# HomeLedEncoder.net
KiCad netlist of a schematic drawn in Altium Designer
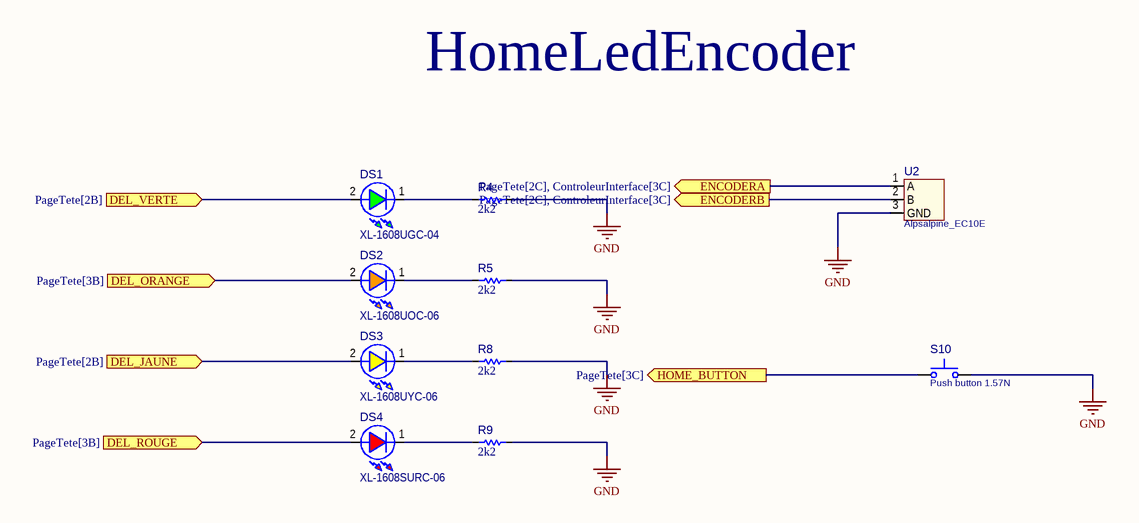
[diagram p0: HomeLedEncoder.SchDoc]

(export (version "E")
  (design (tool "Eeschema 10.0.6"))
  (components
    (comp (ref "DS1")
      (value "XL-1608UGC-04")
      (footprint "D_LED_0603")
      (description "LED Green Clear 40mcd 140deg")
      (libsource (lib "243-336_MP_Manette_ETU") (part "D_LED_GREEN_0603"))
    )
    (comp (ref "DS2")
      (value "XL-1608UOC-06")
      (footprint "D_LED_0603")
      (description "LED Orange Clear")
      (libsource (lib "243-336_MP_Manette_ETU") (part "D_LED_ORANGE_0603"))
    )
    (comp (ref "DS3")
      (value "XL-1608UYC-06")
      (footprint "D_LED_0603")
      (description "LED Yellow Clear")
      (libsource (lib "243-336_MP_Manette_ETU") (part "D_LED_YELLOW_0603"))
    )
    (comp (ref "DS4")
      (value "XL-1608SURC-06")
      (footprint "D_LED_0603")
      (description "LED Red Clear 60mcd 140deg")
      (libsource (lib "243-336_MP_Manette_ETU") (part "D_LED_RED_0603"))
    )
    (comp (ref "R4")
      (value "2k2")
      (footprint "R_1005[0402]")
      (description "Resistor type 1")
      (fields (field (name "TOLERANCE") "1%") (field (name "Comment") "Res 2k2 1% 0402"))
      (libsource (lib "TEP_243-Altium_RLC-Lib") (part "RES008"))
    )
    (comp (ref "R5")
      (value "2k2")
      (footprint "R_1005[0402]")
      (description "Resistor type 1")
      (fields (field (name "TOLERANCE") "1%") (field (name "Comment") "Res 2k2 1% 0402"))
      (libsource (lib "TEP_243-Altium_RLC-Lib") (part "RES008"))
    )
    (comp (ref "R8")
      (value "2k2")
      (footprint "R_1005[0402]")
      (description "Resistor type 1")
      (fields (field (name "TOLERANCE") "1%") (field (name "Comment") "Res 2k2 1% 0402"))
      (libsource (lib "TEP_243-Altium_RLC-Lib") (part "RES008"))
    )
    (comp (ref "R9")
      (value "2k2")
      (footprint "R_1005[0402]")
      (description "Resistor type 1")
      (fields (field (name "TOLERANCE") "1%") (field (name "Comment") "Res 2k2 1% 0402"))
      (libsource (lib "TEP_243-Altium_RLC-Lib") (part "RES008"))
    )
    (comp (ref "S10")
      (value "Push button 1.57N")
      (footprint "S_Alpsalpine_SKPM")
      (fields (field (name "Comment") "SKPMAME010"))
      (libsource (lib "243-336_MP_Manette_ETU") (part "SW_Push_SKPM_157N"))
    )
    (comp (ref "U2")
      (value "Alpsalpine_EC10E")
      (footprint "U_Alpsalpine_EC10E")
      (description "Rotary Encoder TH")
      (fields (field (name "Comment") "EC10E1220503"))
      (libsource (lib "243-336_MP_Manette_ETU") (part "U_Alpsalpine_EC10E"))
    )
  )
  (nets
    (net (code "1") (name "/DEL_JAUNE") (class "Default")
      (node (ref "DS3") (pin "2") (pinfunction "A_2") (pintype "passive"))
    )
    (net (code "2") (name "/DEL_ORANGE") (class "Default")
      (node (ref "DS2") (pin "2") (pinfunction "A_2") (pintype "passive"))
    )
    (net (code "3") (name "/DEL_ROUGE") (class "Default")
      (node (ref "DS4") (pin "2") (pinfunction "A_2") (pintype "passive"))
    )
    (net (code "4") (name "/DEL_VERTE") (class "Default")
      (node (ref "DS1") (pin "2") (pinfunction "A_2") (pintype "passive"))
    )
    (net (code "5") (name "/ENCODERA") (class "Default")
      (node (ref "U2") (pin "1") (pinfunction "A_1") (pintype "passive"))
    )
    (net (code "6") (name "/ENCODERB") (class "Default")
      (node (ref "U2") (pin "2") (pinfunction "B_2") (pintype "passive"))
    )
    (net (code "7") (name "/HOME_BUTTON") (class "Default")
      (node (ref "S10") (pin "1") (pinfunction "1_1") (pintype "passive"))
    )
    (net (code "8") (name "GND") (class "Default")
      (node (ref "R4") (pin "2") (pinfunction "2_2") (pintype "passive"))
      (node (ref "R5") (pin "2") (pinfunction "2_2") (pintype "passive"))
      (node (ref "R8") (pin "2") (pinfunction "2_2") (pintype "passive"))
      (node (ref "R9") (pin "2") (pinfunction "2_2") (pintype "passive"))
      (node (ref "S10") (pin "2") (pinfunction "2_2") (pintype "passive"))
      (node (ref "U2") (pin "3") (pinfunction "GND_3") (pintype "passive"))
    )
    (net (code "9") (name "Net-(DS1-K)") (class "Default")
      (node (ref "DS1") (pin "1") (pinfunction "K_1") (pintype "passive"))
      (node (ref "R4") (pin "1") (pinfunction "1_1") (pintype "passive"))
    )
    (net (code "10") (name "Net-(DS2-K)") (class "Default")
      (node (ref "DS2") (pin "1") (pinfunction "K_1") (pintype "passive"))
      (node (ref "R5") (pin "1") (pinfunction "1_1") (pintype "passive"))
    )
    (net (code "11") (name "Net-(DS3-K)") (class "Default")
      (node (ref "DS3") (pin "1") (pinfunction "K_1") (pintype "passive"))
      (node (ref "R8") (pin "1") (pinfunction "1_1") (pintype "passive"))
    )
    (net (code "12") (name "Net-(DS4-K)") (class "Default")
      (node (ref "DS4") (pin "1") (pinfunction "K_1") (pintype "passive"))
      (node (ref "R9") (pin "1") (pinfunction "1_1") (pintype "passive"))
    )
  )
)
